# hbridge_2_0.net
KiCad netlist of a schematic drawn in EAGLE
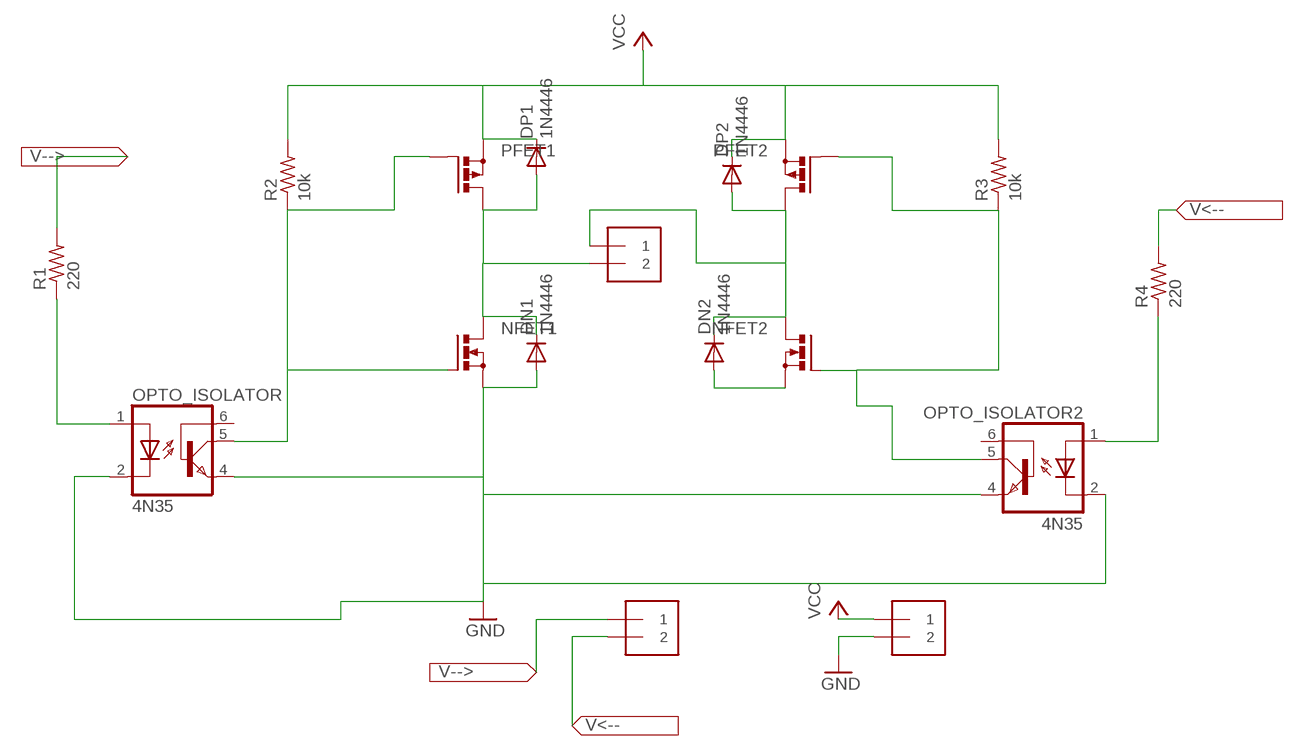
[diagram p0: schematic, sheet 1]

(export (version "E")
  (design (tool "Eeschema 10.0.6"))
  (components
    (comp (ref "ARDUINO")
      (value "1X2-3.5MM")
      (footprint "eagle-import:1X2-3.5MM")
      (libsource (lib "eagle-import") (part "1X2-3.5MM"))
    )
    (comp (ref "DN1")
      (value "1N4446")
      (footprint "eagle-import:DO35-10")
      (libsource (lib "eagle-import") (part "1N4446"))
    )
    (comp (ref "DN2")
      (value "1N4446")
      (footprint "eagle-import:DO35-10")
      (libsource (lib "eagle-import") (part "1N4446"))
    )
    (comp (ref "DP1")
      (value "1N4446")
      (footprint "eagle-import:DO35-10")
      (libsource (lib "eagle-import") (part "1N4446"))
    )
    (comp (ref "DP2")
      (value "1N4446")
      (footprint "eagle-import:DO35-10")
      (libsource (lib "eagle-import") (part "1N4446"))
    )
    (comp (ref "MOTOR")
      (value "1X2-3.5MM")
      (footprint "eagle-import:1X2-3.5MM")
      (libsource (lib "eagle-import") (part "1X2-3.5MM"))
    )
    (comp (ref "NFET1")
      (value "PMOSFET_NTO220BH")
      (footprint "eagle-import:TO220BH")
      (libsource (lib "eagle-import") (part "PMOSFET_NTO220BH"))
    )
    (comp (ref "NFET2")
      (value "PMOSFET_NTO220BH")
      (footprint "eagle-import:TO220BH")
      (libsource (lib "eagle-import") (part "PMOSFET_NTO220BH"))
    )
    (comp (ref "OPTO_ISOLATOR")
      (value "4N35")
      (footprint "eagle-import:DIL06")
      (fields (field (name "MF") "FAIRCHILD SEMICONDUCTOR"))
      (libsource (lib "eagle-import") (part "4N35"))
    )
    (comp (ref "OPTO_ISOLATOR2")
      (value "4N35")
      (footprint "eagle-import:DIL06")
      (fields (field (name "MF") "FAIRCHILD SEMICONDUCTOR"))
      (libsource (lib "eagle-import") (part "4N35"))
    )
    (comp (ref "PFET1")
      (value "PMOSFET_PTO220BH")
      (footprint "eagle-import:TO220BH")
      (libsource (lib "eagle-import") (part "PMOSFET_PTO220BH"))
    )
    (comp (ref "PFET2")
      (value "PMOSFET_PTO220BH")
      (footprint "eagle-import:TO220BH")
      (libsource (lib "eagle-import") (part "PMOSFET_PTO220BH"))
    )
    (comp (ref "POWER")
      (value "1X2-3.5MM")
      (footprint "eagle-import:1X2-3.5MM")
      (libsource (lib "eagle-import") (part "1X2-3.5MM"))
    )
    (comp (ref "R1")
      (value "220")
      (footprint "eagle-import:0207_15")
      (libsource (lib "eagle-import") (part "R-US_0207/15"))
    )
    (comp (ref "R2")
      (value "10k")
      (footprint "eagle-import:0207_15")
      (libsource (lib "eagle-import") (part "R-US_0207/15"))
    )
    (comp (ref "R3")
      (value "10k")
      (footprint "eagle-import:0207_15")
      (libsource (lib "eagle-import") (part "R-US_0207/15"))
    )
    (comp (ref "R4")
      (value "220")
      (footprint "eagle-import:0207_15")
      (libsource (lib "eagle-import") (part "R-US_0207/15"))
    )
  )
  (nets
    (net (code "1") (name "/ARDUINO_A") (class "Default")
      (node (ref "ARDUINO") (pin "1") (pinfunction "1_1") (pintype "passive"))
      (node (ref "R1") (pin "2") (pinfunction "2_2") (pintype "passive"))
    )
    (net (code "2") (name "/ARDUINO_B") (class "Default")
      (node (ref "ARDUINO") (pin "2") (pinfunction "2_2") (pintype "passive"))
      (node (ref "R4") (pin "2") (pinfunction "2_2") (pintype "passive"))
    )
    (net (code "3") (name "GND") (class "Default")
      (node (ref "DN1") (pin "A") (pinfunction "A_A") (pintype "passive"))
      (node (ref "NFET1") (pin "S") (pinfunction "S_S") (pintype "passive"))
      (node (ref "OPTO_ISOLATOR") (pin "2") (pinfunction "C_2") (pintype "passive"))
      (node (ref "OPTO_ISOLATOR") (pin "4") (pinfunction "EMI_4") (pintype "passive"))
      (node (ref "OPTO_ISOLATOR2") (pin "2") (pinfunction "C_2") (pintype "passive"))
      (node (ref "OPTO_ISOLATOR2") (pin "4") (pinfunction "EMI_4") (pintype "passive"))
      (node (ref "POWER") (pin "2") (pinfunction "2_2") (pintype "passive"))
    )
    (net (code "4") (name "Net-(DN1-PadC)") (class "Default")
      (node (ref "DN1") (pin "C") (pinfunction "C_C") (pintype "passive"))
      (node (ref "DP1") (pin "A") (pinfunction "A_A") (pintype "passive"))
      (node (ref "MOTOR") (pin "2") (pinfunction "2_2") (pintype "passive"))
      (node (ref "NFET1") (pin "D") (pinfunction "D_D") (pintype "passive"))
      (node (ref "PFET1") (pin "D") (pinfunction "D_D") (pintype "passive"))
    )
    (net (code "5") (name "Net-(DN2-PadA)") (class "Default")
      (node (ref "DN2") (pin "A") (pinfunction "A_A") (pintype "passive"))
      (node (ref "NFET2") (pin "S") (pinfunction "S_S") (pintype "passive"))
    )
    (net (code "6") (name "Net-(DN2-PadC)") (class "Default")
      (node (ref "DN2") (pin "C") (pinfunction "C_C") (pintype "passive"))
      (node (ref "DP2") (pin "A") (pinfunction "A_A") (pintype "passive"))
      (node (ref "MOTOR") (pin "1") (pinfunction "1_1") (pintype "passive"))
      (node (ref "NFET2") (pin "D") (pinfunction "D_D") (pintype "passive"))
      (node (ref "PFET2") (pin "D") (pinfunction "D_D") (pintype "passive"))
    )
    (net (code "7") (name "Net-(OPTO_ISOLATOR-A)") (class "Default")
      (node (ref "OPTO_ISOLATOR") (pin "1") (pinfunction "A_1") (pintype "passive"))
      (node (ref "R1") (pin "1") (pinfunction "1_1") (pintype "passive"))
    )
    (net (code "8") (name "Net-(OPTO_ISOLATOR-COL)") (class "Default")
      (node (ref "NFET1") (pin "G") (pinfunction "G_G") (pintype "passive"))
      (node (ref "OPTO_ISOLATOR") (pin "5") (pinfunction "COL_5") (pintype "passive"))
      (node (ref "PFET1") (pin "G") (pinfunction "G_G") (pintype "passive"))
      (node (ref "R2") (pin "1") (pinfunction "1_1") (pintype "passive"))
    )
    (net (code "9") (name "Net-(OPTO_ISOLATOR2-A)") (class "Default")
      (node (ref "OPTO_ISOLATOR2") (pin "1") (pinfunction "A_1") (pintype "passive"))
      (node (ref "R4") (pin "1") (pinfunction "1_1") (pintype "passive"))
    )
    (net (code "10") (name "Net-(OPTO_ISOLATOR2-COL)") (class "Default")
      (node (ref "NFET2") (pin "G") (pinfunction "G_G") (pintype "passive"))
      (node (ref "OPTO_ISOLATOR2") (pin "5") (pinfunction "COL_5") (pintype "passive"))
      (node (ref "PFET2") (pin "G") (pinfunction "G_G") (pintype "passive"))
      (node (ref "R3") (pin "1") (pinfunction "1_1") (pintype "passive"))
    )
    (net (code "11") (name "VCC") (class "Default")
      (node (ref "DP1") (pin "C") (pinfunction "C_C") (pintype "passive"))
      (node (ref "DP2") (pin "C") (pinfunction "C_C") (pintype "passive"))
      (node (ref "PFET1") (pin "S") (pinfunction "S_S") (pintype "passive"))
      (node (ref "PFET2") (pin "S") (pinfunction "S_S") (pintype "passive"))
      (node (ref "POWER") (pin "1") (pinfunction "1_1") (pintype "passive"))
      (node (ref "R2") (pin "2") (pinfunction "2_2") (pintype "passive"))
      (node (ref "R3") (pin "2") (pinfunction "2_2") (pintype "passive"))
    )
    (net (code "12") (name "unconnected-(OPTO_ISOLATOR-BAS-Pad6)") (class "Default")
      (node (ref "OPTO_ISOLATOR") (pin "6") (pinfunction "BAS_6") (pintype "passive"))
    )
    (net (code "13") (name "unconnected-(OPTO_ISOLATOR2-BAS-Pad6)") (class "Default")
      (node (ref "OPTO_ISOLATOR2") (pin "6") (pinfunction "BAS_6") (pintype "passive"))
    )
  )
)
